# RAK11720.net
KiCad netlist of a schematic drawn in Altium Designer
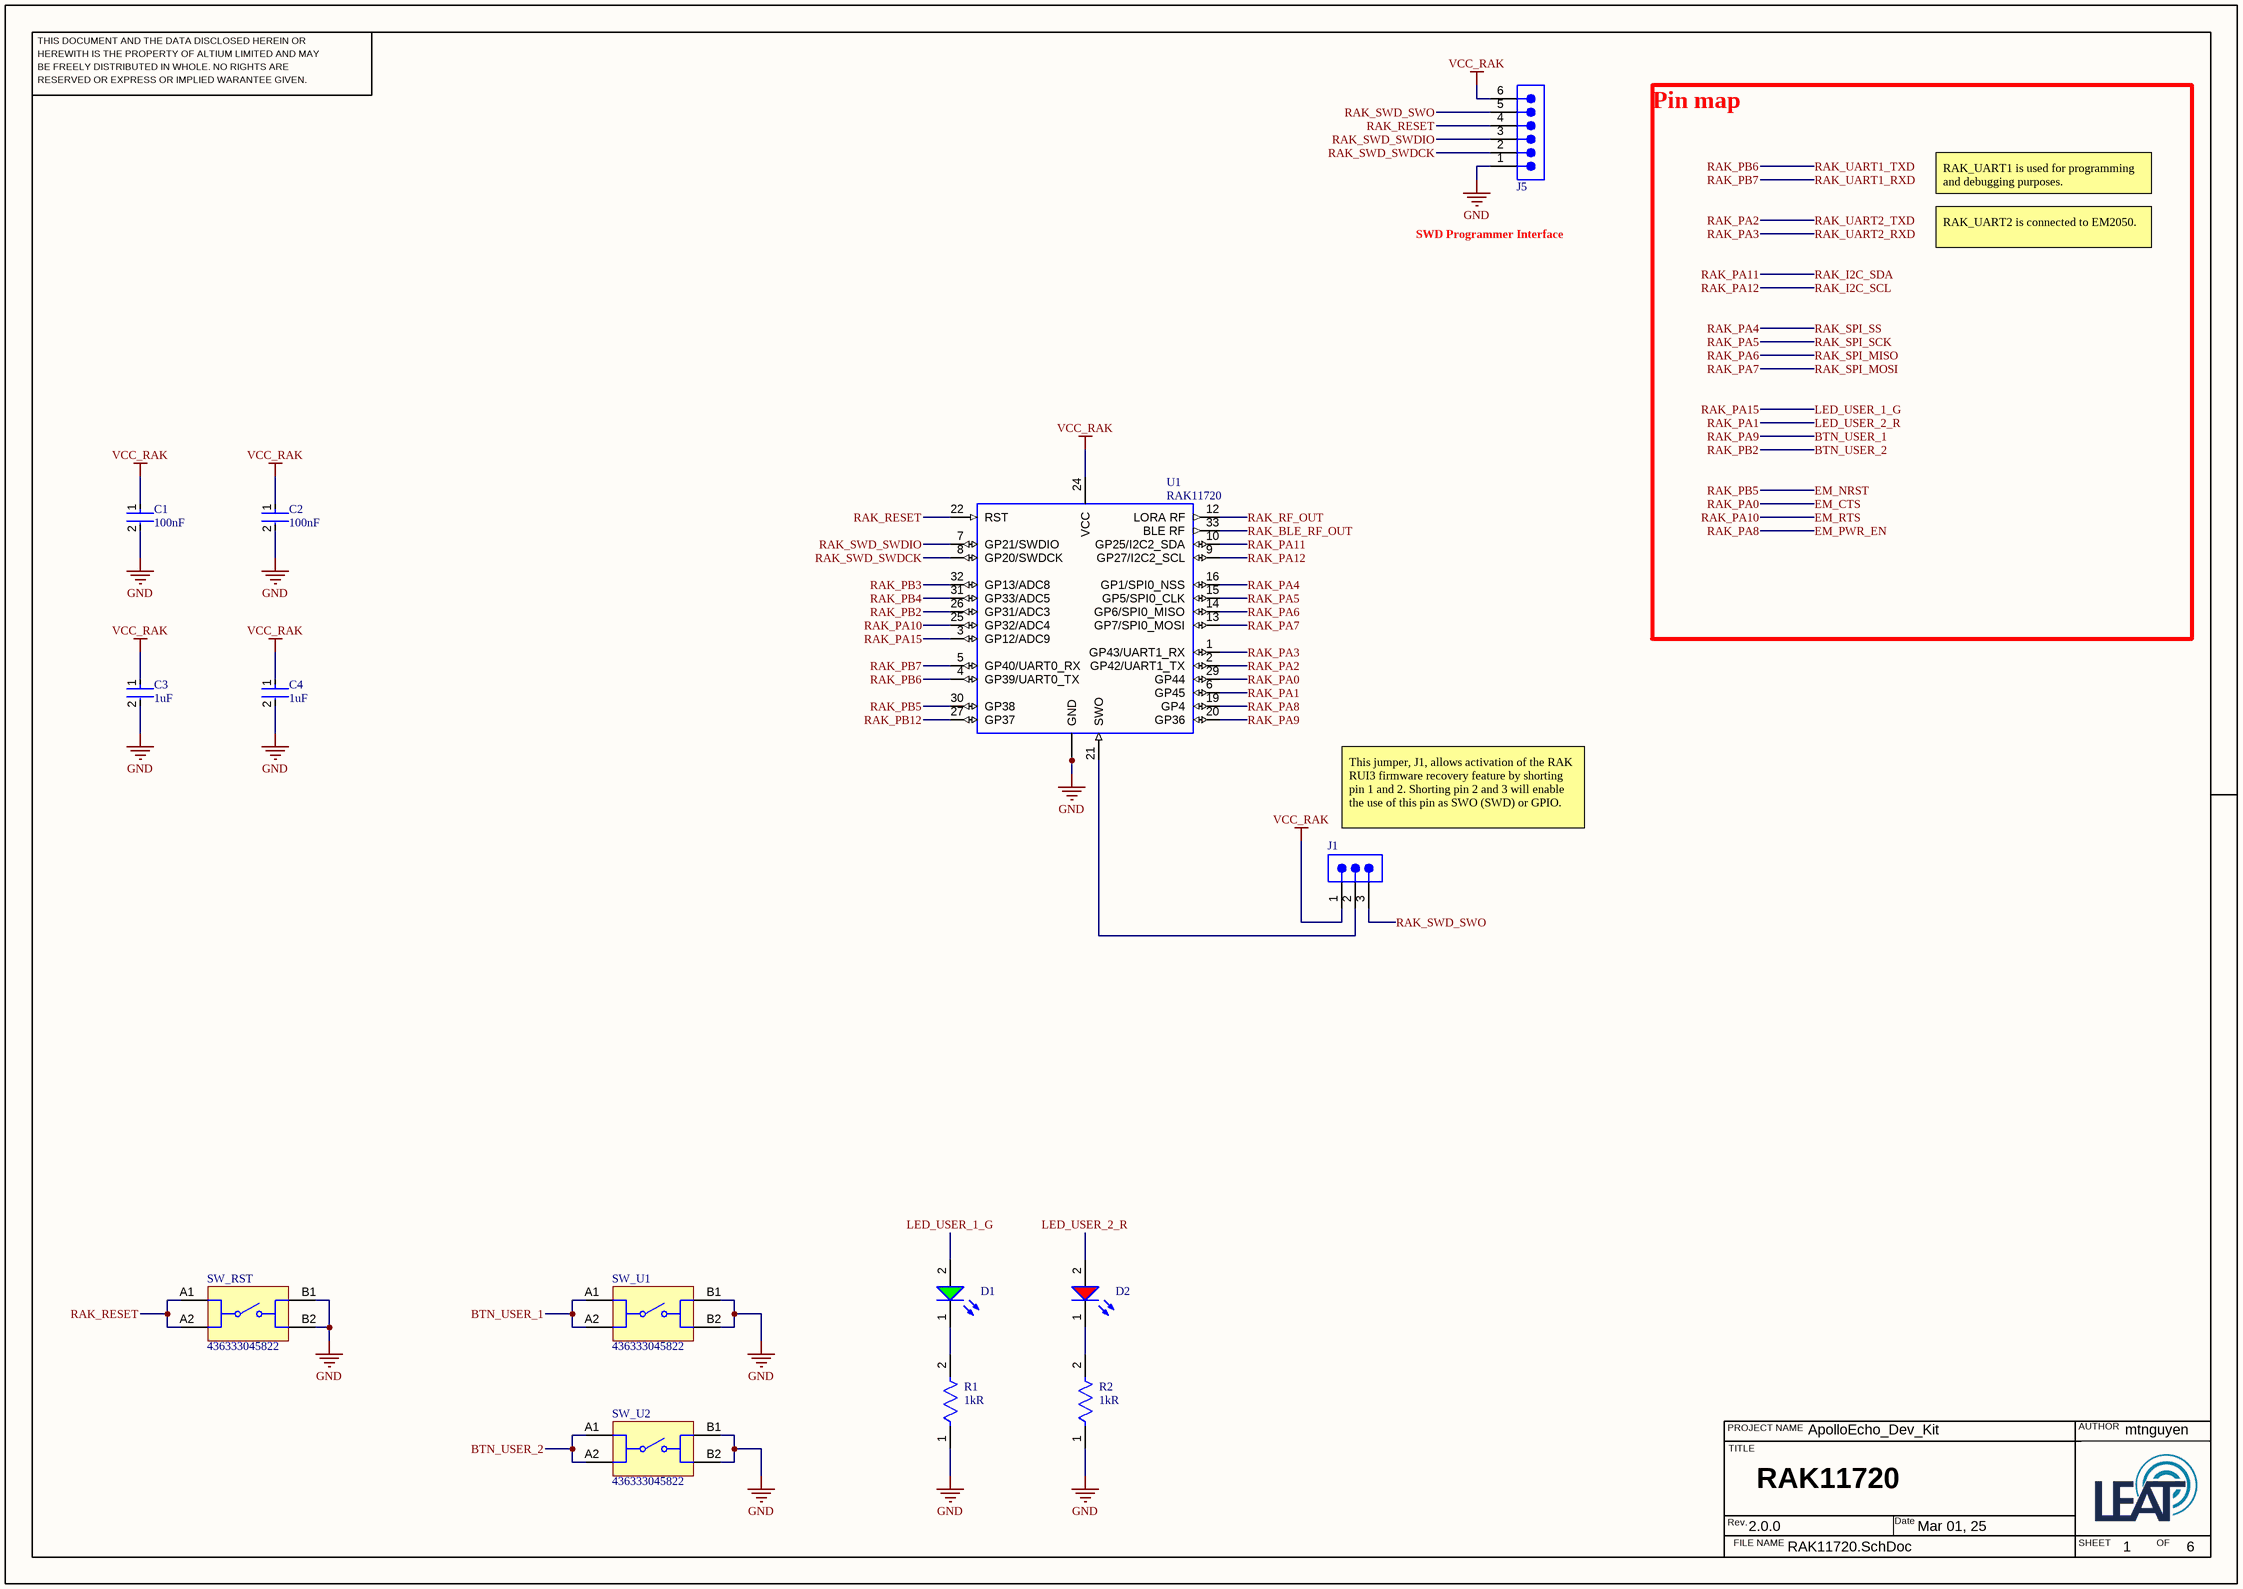
[diagram p0: RAK11720.SchDoc]

(export (version "E")
  (design (tool "Eeschema 10.0.6"))
  (components
    (comp (ref "C1")
      (value "0402ZD104KAT2A")
      (footprint "FP-0402-L_1_0_1-W_0_5_0_1-IPC_C")
      (description "General Purpose Ceramic Capacitor, 0402, 100nF, 10%, X5R, 15%, 10V")
      (fields
        (field (name "VOLTAGE") "10V")
        (field (name "TOLERANCE") "10%")
        (field (name "CAPACITANCE") "100nF")
      )
      (libsource (lib "ApolloEcho_Dev_Kit") (part "b4654b650e69147ec39a6b967a45e02"))
    )
    (comp (ref "C2")
      (value "0402ZD104KAT2A")
      (footprint "FP-0402-L_1_0_1-W_0_5_0_1-IPC_C")
      (description "General Purpose Ceramic Capacitor, 0402, 100nF, 10%, X5R, 15%, 10V")
      (fields
        (field (name "VOLTAGE") "10V")
        (field (name "TOLERANCE") "10%")
        (field (name "CAPACITANCE") "100nF")
      )
      (libsource (lib "ApolloEcho_Dev_Kit") (part "b4654b650e69147ec39a6b967a45e02"))
    )
    (comp (ref "C3")
      (value "EMK105BJ105KV-F")
      (footprint "FP-0402-L_1_0_0_05-W_0_5-IPC_A")
      (description "None")
      (fields (field (name "TOLERANCE") "10%") (field (name "CAPACITANCE") "1uF"))
      (libsource (lib "ApolloEcho_Dev_Kit") (part "b4654b650e69147ec39a6b967a45e02"))
    )
    (comp (ref "C4")
      (value "EMK105BJ105KV-F")
      (footprint "FP-0402-L_1_0_0_05-W_0_5-IPC_A")
      (description "None")
      (fields (field (name "TOLERANCE") "10%") (field (name "CAPACITANCE") "1uF"))
      (libsource (lib "ApolloEcho_Dev_Kit") (part "b4654b650e69147ec39a6b967a45e02"))
    )
    (comp (ref "D1")
      (value "150060VS75000")
      (footprint "WL-SMCW_0603_150060xx75000")
      (description "WURTH ELEKTRONIK - 150060VS75000 - LED, Green, SMD, 0603, 30 mA, 2 V, 570 nm")
      (libsource (lib "ApolloEcho_Dev_Kit") (part "LED_Green_2A-1K"))
    )
    (comp (ref "D2")
      (value "150060RS75000")
      (footprint "WL-SMCW_0603_150060xx75000")
      (description "LED Low-Power Uni-Color Red 630nm 2V 2-Pin Chip 0603(1608Metric) T/R")
      (libsource (lib "ApolloEcho_Dev_Kit") (part "LED_Red_2A-1K"))
    )
    (comp (ref "J1")
      (value "61300311121")
      (footprint "61300311121")
      (libsource (lib "ApolloEcho_Dev_Kit") (part "Header_Male_1R_03P"))
    )
    (comp (ref "J5")
      (value "61300611121")
      (footprint "61300611121")
      (libsource (lib "ApolloEcho_Dev_Kit") (part "Header_Male_1R_06P"))
    )
    (comp (ref "R1")
      (value "RMCF0402FT1K00")
      (footprint "FP-RMCF0402-IPC_A")
      (description "1kΩ ±1% 0.063W 0402 Thick Film Chip Resistor AEC-Q200 compliant")
      (fields (field (name "TOLERANCE") "1%") (field (name "RESISTANCE") "1kR"))
      (libsource (lib "ApolloEcho_Dev_Kit") (part "1029c3af85768c4190bb7ad29bc67b5"))
    )
    (comp (ref "R2")
      (value "RMCF0402FT1K00")
      (footprint "FP-RMCF0402-IPC_A")
      (description "1kΩ ±1% 0.063W 0402 Thick Film Chip Resistor AEC-Q200 compliant")
      (fields (field (name "TOLERANCE") "1%") (field (name "RESISTANCE") "1kR"))
      (libsource (lib "ApolloEcho_Dev_Kit") (part "1029c3af85768c4190bb7ad29bc67b5"))
    )
    (comp (ref "SW_RST")
      (value "436333045822")
      (footprint "436333045822")
      (libsource (lib "ApolloEcho_Dev_Kit") (part "SPST-NO_4P"))
    )
    (comp (ref "SW_U1")
      (value "436333045822")
      (footprint "436333045822")
      (libsource (lib "ApolloEcho_Dev_Kit") (part "SPST-NO_4P"))
    )
    (comp (ref "SW_U2")
      (value "436333045822")
      (footprint "436333045822")
      (libsource (lib "ApolloEcho_Dev_Kit") (part "SPST-NO_4P"))
    )
    (comp (ref "U1")
      (value "RAK11720")
      (footprint "RAK11720")
      (description "RAK11720 Ambiq Apollo3 Blue SX1262 LoRa Bluetooth Module for LoRaWAN")
      (fields (field (name "MP") "RAK3172") (field (name "MF") "Shenzhen RAKwireless Technology Co.,Ltd."))
      (libsource (lib "ApolloEcho_Dev_Kit") (part "RAK11720"))
    )
  )
  (nets
    (net (code "1") (name "/BTN_USER_1") (class "Default")
      (node (ref "SW_U1") (pin "A1") (pinfunction "A1_A1") (pintype "passive"))
      (node (ref "SW_U1") (pin "A2") (pinfunction "A2_A2") (pintype "passive"))
      (node (ref "U1") (pin "20") (pinfunction "GP36_20") (pintype "bidirectional"))
    )
    (net (code "2") (name "/BTN_USER_2") (class "Default")
      (node (ref "SW_U2") (pin "A1") (pinfunction "A1_A1") (pintype "passive"))
      (node (ref "SW_U2") (pin "A2") (pinfunction "A2_A2") (pintype "passive"))
      (node (ref "U1") (pin "26") (pinfunction "GP31/ADC3_26") (pintype "bidirectional"))
    )
    (net (code "3") (name "/EM_CTS") (class "Default")
      (node (ref "U1") (pin "29") (pinfunction "GP44_29") (pintype "bidirectional"))
    )
    (net (code "4") (name "/EM_NRST") (class "Default")
      (node (ref "U1") (pin "30") (pinfunction "GP38_30") (pintype "bidirectional"))
    )
    (net (code "5") (name "/EM_PWR_EN") (class "Default")
      (node (ref "U1") (pin "19") (pinfunction "GP4_19") (pintype "bidirectional"))
    )
    (net (code "6") (name "/EM_RTS") (class "Default")
      (node (ref "U1") (pin "25") (pinfunction "GP32/ADC4_25") (pintype "bidirectional"))
    )
    (net (code "7") (name "/LED_USER_1_G") (class "Default")
      (node (ref "D1") (pin "2") (pinfunction "A_2") (pintype "passive"))
      (node (ref "U1") (pin "3") (pinfunction "GP12/ADC9_3") (pintype "bidirectional"))
    )
    (net (code "8") (name "/LED_USER_2_R") (class "Default")
      (node (ref "D2") (pin "2") (pinfunction "A_2") (pintype "passive"))
      (node (ref "U1") (pin "6") (pinfunction "GP45_6") (pintype "bidirectional"))
    )
    (net (code "9") (name "/RAK_BLE_RF_OUT") (class "Default")
      (node (ref "U1") (pin "33") (pinfunction "BLE_RF_33") (pintype "output"))
    )
    (net (code "10") (name "/RAK_I2C_SCL") (class "Default")
      (node (ref "U1") (pin "9") (pinfunction "GP27/I2C2_SCL_9") (pintype "bidirectional"))
    )
    (net (code "11") (name "/RAK_I2C_SDA") (class "Default")
      (node (ref "U1") (pin "10") (pinfunction "GP25/I2C2_SDA_10") (pintype "bidirectional"))
    )
    (net (code "12") (name "/RAK_PA2") (class "Default")
      (node (ref "U1") (pin "2") (pinfunction "GP42/UART1_TX_2") (pintype "bidirectional"))
    )
    (net (code "13") (name "/RAK_PA3") (class "Default")
      (node (ref "U1") (pin "1") (pinfunction "GP43/UART1_RX_1") (pintype "bidirectional"))
    )
    (net (code "14") (name "/RAK_PA4") (class "Default")
      (node (ref "U1") (pin "16") (pinfunction "GP1/SPI0_NSS_16") (pintype "bidirectional"))
    )
    (net (code "15") (name "/RAK_PA5") (class "Default")
      (node (ref "U1") (pin "15") (pinfunction "GP5/SPI0_CLK_15") (pintype "bidirectional"))
    )
    (net (code "16") (name "/RAK_PA6") (class "Default")
      (node (ref "U1") (pin "14") (pinfunction "GP6/SPI0_MISO_14") (pintype "bidirectional"))
    )
    (net (code "17") (name "/RAK_PA7") (class "Default")
      (node (ref "U1") (pin "13") (pinfunction "GP7/SPI0_MOSI_13") (pintype "bidirectional"))
    )
    (net (code "18") (name "/RAK_PB3") (class "Default")
      (node (ref "U1") (pin "32") (pinfunction "GP13/ADC8_32") (pintype "bidirectional"))
    )
    (net (code "19") (name "/RAK_PB4") (class "Default")
      (node (ref "U1") (pin "31") (pinfunction "GP33/ADC5_31") (pintype "bidirectional"))
    )
    (net (code "20") (name "/RAK_PB6") (class "Default")
      (node (ref "U1") (pin "4") (pinfunction "GP39/UART0_TX_4") (pintype "bidirectional"))
    )
    (net (code "21") (name "/RAK_PB7") (class "Default")
      (node (ref "U1") (pin "5") (pinfunction "GP40/UART0_RX_5") (pintype "bidirectional"))
    )
    (net (code "22") (name "/RAK_PB12") (class "Default")
      (node (ref "U1") (pin "27") (pinfunction "GP37_27") (pintype "bidirectional"))
    )
    (net (code "23") (name "/RAK_RESET") (class "Default")
      (node (ref "J5") (pin "4") (pinfunction "4_4") (pintype "passive"))
      (node (ref "SW_RST") (pin "A1") (pinfunction "A1_A1") (pintype "passive"))
      (node (ref "SW_RST") (pin "A2") (pinfunction "A2_A2") (pintype "passive"))
      (node (ref "U1") (pin "22") (pinfunction "RST_22") (pintype "input"))
    )
    (net (code "24") (name "/RAK_RF_OUT") (class "Default")
      (node (ref "U1") (pin "12") (pinfunction "LORA_RF_12") (pintype "output"))
    )
    (net (code "25") (name "/RAK_SWD_SWDCK") (class "Default")
      (node (ref "J5") (pin "2") (pinfunction "2_2") (pintype "passive"))
      (node (ref "U1") (pin "8") (pinfunction "GP20/SWDCK_8") (pintype "bidirectional"))
    )
    (net (code "26") (name "/RAK_SWD_SWDIO") (class "Default")
      (node (ref "J5") (pin "3") (pinfunction "3_3") (pintype "passive"))
      (node (ref "U1") (pin "7") (pinfunction "GP21/SWDIO_7") (pintype "bidirectional"))
    )
    (net (code "27") (name "/RAK_SWD_SWO") (class "Default")
      (node (ref "J1") (pin "3") (pinfunction "3_3") (pintype "passive"))
      (node (ref "J5") (pin "5") (pinfunction "5_5") (pintype "passive"))
    )
    (net (code "28") (name "GND") (class "Default")
      (node (ref "C1") (pin "2") (pinfunction "2_2") (pintype "passive"))
      (node (ref "C2") (pin "2") (pinfunction "2_2") (pintype "passive"))
      (node (ref "C3") (pin "2") (pinfunction "2_2") (pintype "passive"))
      (node (ref "C4") (pin "2") (pinfunction "2_2") (pintype "passive"))
      (node (ref "J5") (pin "1") (pinfunction "1_1") (pintype "passive"))
      (node (ref "R1") (pin "1") (pinfunction "1_1") (pintype "passive"))
      (node (ref "R2") (pin "1") (pinfunction "1_1") (pintype "passive"))
      (node (ref "SW_RST") (pin "B1") (pinfunction "B1_B1") (pintype "passive"))
      (node (ref "SW_RST") (pin "B2") (pinfunction "B2_B2") (pintype "passive"))
      (node (ref "SW_U1") (pin "B1") (pinfunction "B1_B1") (pintype "passive"))
      (node (ref "SW_U1") (pin "B2") (pinfunction "B2_B2") (pintype "passive"))
      (node (ref "SW_U2") (pin "B1") (pinfunction "B1_B1") (pintype "passive"))
      (node (ref "SW_U2") (pin "B2") (pinfunction "B2_B2") (pintype "passive"))
      (node (ref "U1") (pin "11") (pinfunction "GND_11") (pintype "power_in"))
      (node (ref "U1") (pin "17") (pinfunction "GND_17") (pintype "power_in"))
      (node (ref "U1") (pin "18") (pinfunction "GND_18") (pintype "power_in"))
      (node (ref "U1") (pin "23") (pinfunction "GND_23") (pintype "power_in"))
      (node (ref "U1") (pin "28") (pinfunction "GND_28") (pintype "power_in"))
      (node (ref "U1") (pin "34") (pinfunction "GND_34") (pintype "power_in"))
    )
    (net (code "29") (name "Net-(D1-K)") (class "Default")
      (node (ref "D1") (pin "1") (pinfunction "K_1") (pintype "passive"))
      (node (ref "R1") (pin "2") (pinfunction "2_2") (pintype "passive"))
    )
    (net (code "30") (name "Net-(D2-K)") (class "Default")
      (node (ref "D2") (pin "1") (pinfunction "K_1") (pintype "passive"))
      (node (ref "R2") (pin "2") (pinfunction "2_2") (pintype "passive"))
    )
    (net (code "31") (name "Net-(U1-SWO)") (class "Default")
      (node (ref "J1") (pin "2") (pinfunction "2_2") (pintype "passive"))
      (node (ref "U1") (pin "21") (pinfunction "SWO_21") (pintype "input"))
    )
    (net (code "32") (name "VCC_RAK") (class "Default")
      (node (ref "C1") (pin "1") (pinfunction "1_1") (pintype "passive"))
      (node (ref "C2") (pin "1") (pinfunction "1_1") (pintype "passive"))
      (node (ref "C3") (pin "1") (pinfunction "1_1") (pintype "passive"))
      (node (ref "C4") (pin "1") (pinfunction "1_1") (pintype "passive"))
      (node (ref "J1") (pin "1") (pinfunction "1_1") (pintype "passive"))
      (node (ref "J5") (pin "6") (pinfunction "6_6") (pintype "passive"))
      (node (ref "U1") (pin "24") (pinfunction "VCC_24") (pintype "power_in"))
    )
  )
)
